# transistormodule.net
KiCad netlist of a schematic drawn in Altium Designer
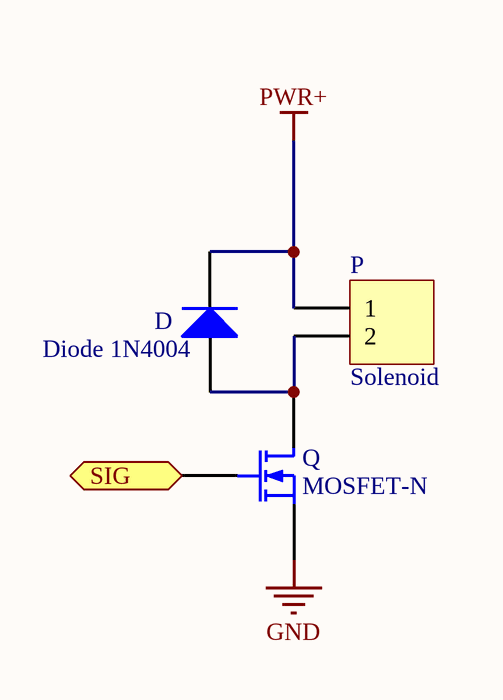
[diagram p0: transistormodule.SchDoc]

(export (version "E")
  (design (tool "Eeschema 10.0.6"))
  (components
    (comp (ref "D")
      (value "Diode 1N4004")
      (footprint "DO-41")
      (description "1 Amp General Purpose Rectifier")
      (fields (field (name "PUBLISHER") "Altium Limited"))
      (libsource (lib "Miscellaneous Devices") (part "Diode 1N4004"))
    )
    (comp (ref "P")
      (value "Solenoid")
      (footprint "HDR1X2")
      (description "Header, 2-Pin")
      (fields (field (name "PUBLISHER") "Altium Limited"))
      (libsource (lib "Miscellaneous Connectors") (part "Header 2"))
    )
    (comp (ref "Q")
      (value "MOSFET-N")
      (footprint "Miscellaneous Devices:TO-220-AB")
      (description "N-Channel MOSFET")
      (fields (field (name "PUBLISHER") "Altium Limited"))
      (libsource (lib "Miscellaneous Devices") (part "MOSFET-N"))
    )
  )
  (nets
    (net (code "1") (name "/SIG") (class "Default")
      (node (ref "Q") (pin "2") (pinfunction "G_2") (pintype "passive"))
    )
    (net (code "2") (name "GND") (class "Default")
      (node (ref "Q") (pin "3") (pinfunction "S_3") (pintype "passive"))
    )
    (net (code "3") (name "Net-(D-A)") (class "Default")
      (node (ref "D") (pin "1") (pinfunction "A_1") (pintype "passive"))
      (node (ref "P") (pin "2") (pinfunction "2_2") (pintype "passive"))
      (node (ref "Q") (pin "1") (pinfunction "D_1") (pintype "passive"))
    )
    (net (code "4") (name "PWR+") (class "Default")
      (node (ref "D") (pin "2") (pinfunction "K_2") (pintype "passive"))
      (node (ref "P") (pin "1") (pinfunction "1_1") (pintype "passive"))
    )
  )
)
